# Launchpad_Board.net
KiCad netlist of a schematic drawn in EAGLE
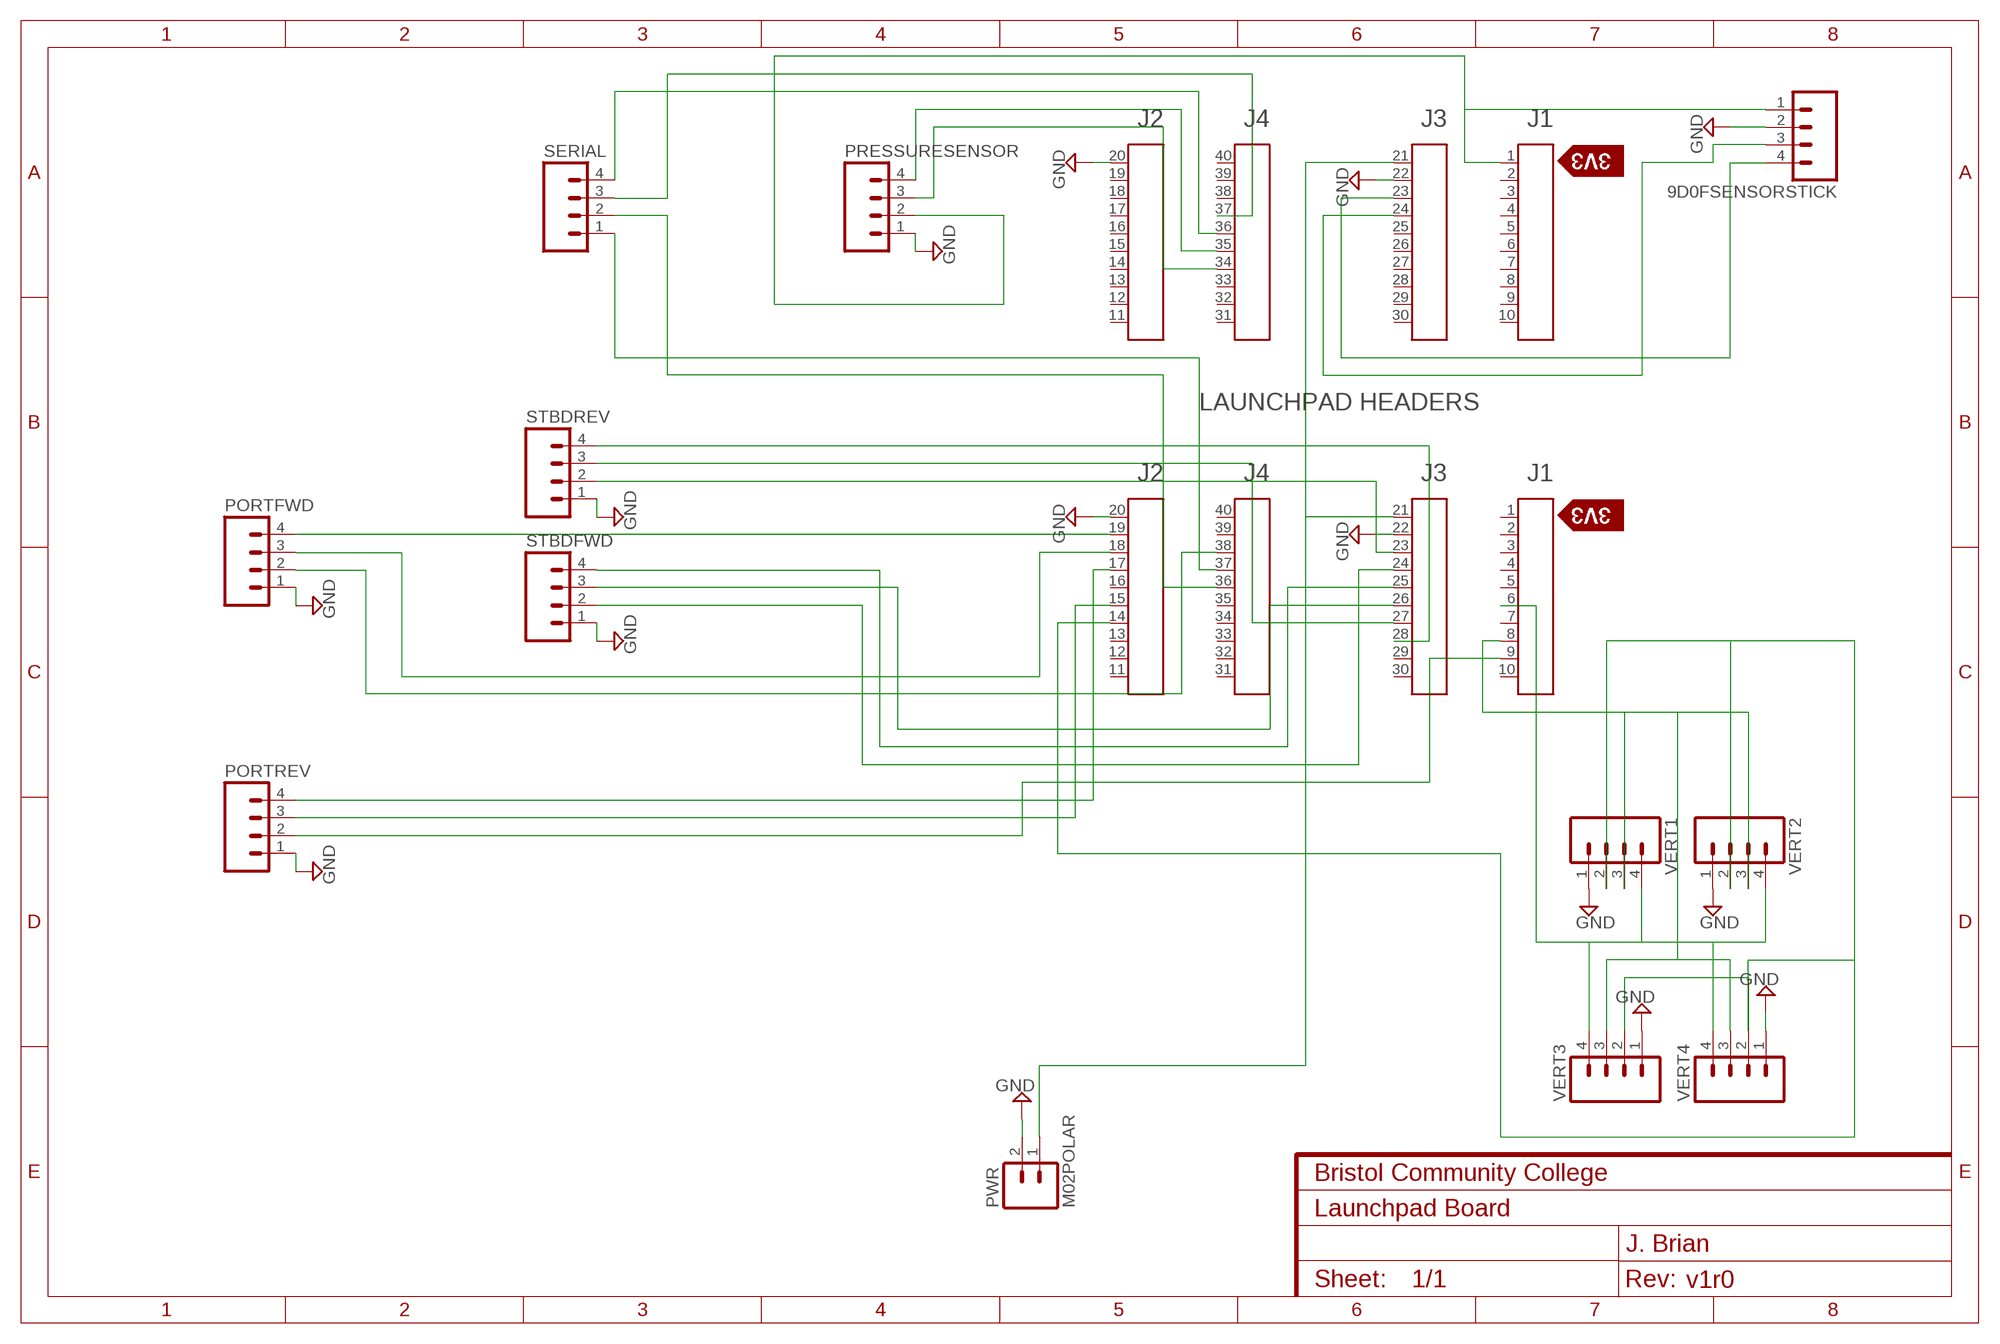
[diagram p0: schematic, sheet 1]

(export (version "E")
  (design (tool "Eeschema 10.0.6"))
  (components
    (comp (ref "9D0FSENSORSTICK")
      (value "M04PTH")
      (footprint "eagle-import:1X04")
      (libsource (lib "eagle-import") (part "M04PTH"))
    )
    (comp (ref "A1")
      (value "HEADER4X10-BOOSTERPACK")
      (footprint "eagle-import:4X10-BOOSTERPACK")
      (libsource (lib "eagle-import") (part "HEADER4X10-BOOSTERPACK"))
    )
    (comp (ref "A2")
      (value "HEADER4X10-BOOSTERPACK")
      (footprint "eagle-import:4X10-BOOSTERPACK")
      (libsource (lib "eagle-import") (part "HEADER4X10-BOOSTERPACK"))
    )
    (comp (ref "PORTFWD")
      (value "M04POLAR_LOCK")
      (footprint "eagle-import:MOLEX-1X4_LOCK")
      (libsource (lib "eagle-import") (part "M04POLAR_LOCK"))
    )
    (comp (ref "PORTREV")
      (value "M04POLAR_LOCK")
      (footprint "eagle-import:MOLEX-1X4_LOCK")
      (libsource (lib "eagle-import") (part "M04POLAR_LOCK"))
    )
    (comp (ref "PRESSURESENSOR")
      (value "M04POLAR")
      (footprint "eagle-import:MOLEX-1X4")
      (libsource (lib "eagle-import") (part "M04POLAR"))
    )
    (comp (ref "PWR")
      (value "M02POLAR")
      (footprint "eagle-import:MOLEX-1X2")
      (libsource (lib "eagle-import") (part "M02POLAR"))
    )
    (comp (ref "SERIAL")
      (value "M04POLAR_LOCK")
      (footprint "eagle-import:MOLEX-1X4_LOCK")
      (libsource (lib "eagle-import") (part "M04POLAR_LOCK"))
    )
    (comp (ref "STBDFWD")
      (value "M04POLAR_LOCK")
      (footprint "eagle-import:MOLEX-1X4_LOCK")
      (libsource (lib "eagle-import") (part "M04POLAR_LOCK"))
    )
    (comp (ref "STBDREV")
      (value "M04POLAR_LOCK")
      (footprint "eagle-import:MOLEX-1X4_LOCK")
      (libsource (lib "eagle-import") (part "M04POLAR_LOCK"))
    )
    (comp (ref "U$3")
      (value "SILK_3V3_TAG")
      (footprint "eagle-import:SILK_3V3_TAG")
      (libsource (lib "eagle-import") (part "SILK_3V3_TAG"))
    )
    (comp (ref "U$4")
      (value "SILK_3V3_TAG")
      (footprint "eagle-import:SILK_3V3_TAG")
      (libsource (lib "eagle-import") (part "SILK_3V3_TAG"))
    )
    (comp (ref "VERT1")
      (value "M04POLAR_LOCK")
      (footprint "eagle-import:MOLEX-1X4_LOCK")
      (libsource (lib "eagle-import") (part "M04POLAR_LOCK"))
    )
    (comp (ref "VERT2")
      (value "M04POLAR_LOCK")
      (footprint "eagle-import:MOLEX-1X4_LOCK")
      (libsource (lib "eagle-import") (part "M04POLAR_LOCK"))
    )
    (comp (ref "VERT3")
      (value "M04POLAR_LOCK")
      (footprint "eagle-import:MOLEX-1X4_LOCK")
      (libsource (lib "eagle-import") (part "M04POLAR_LOCK"))
    )
    (comp (ref "VERT4")
      (value "M04POLAR_LOCK")
      (footprint "eagle-import:MOLEX-1X4_LOCK")
      (libsource (lib "eagle-import") (part "M04POLAR_LOCK"))
    )
  )
  (nets
    (net (code "1") (name "/N$9") (class "Default")
      (node (ref "A2") (pin "8") (pinfunction "P$8_8") (pintype "bidirectional"))
      (node (ref "VERT1") (pin "3") (pinfunction "3_3") (pintype "passive"))
      (node (ref "VERT2") (pin "3") (pinfunction "3_3") (pintype "passive"))
      (node (ref "VERT3") (pin "3") (pinfunction "3_3") (pintype "passive"))
      (node (ref "VERT4") (pin "3") (pinfunction "3_3") (pintype "passive"))
    )
    (net (code "2") (name "GND") (class "Default")
      (node (ref "9D0FSENSORSTICK") (pin "2") (pinfunction "2_2") (pintype "passive"))
      (node (ref "A1") (pin "20") (pinfunction "P$20_20") (pintype "bidirectional"))
      (node (ref "A1") (pin "22") (pinfunction "P$22_22") (pintype "bidirectional"))
      (node (ref "A2") (pin "20") (pinfunction "P$20_20") (pintype "bidirectional"))
      (node (ref "A2") (pin "22") (pinfunction "P$22_22") (pintype "bidirectional"))
      (node (ref "PORTFWD") (pin "1") (pinfunction "1_1") (pintype "passive"))
      (node (ref "PORTREV") (pin "1") (pinfunction "1_1") (pintype "passive"))
      (node (ref "PRESSURESENSOR") (pin "1") (pinfunction "1_1") (pintype "passive"))
      (node (ref "PWR") (pin "2") (pinfunction "2_2") (pintype "passive"))
      (node (ref "STBDFWD") (pin "1") (pinfunction "1_1") (pintype "passive"))
      (node (ref "STBDREV") (pin "1") (pinfunction "1_1") (pintype "passive"))
      (node (ref "VERT1") (pin "1") (pinfunction "1_1") (pintype "passive"))
      (node (ref "VERT2") (pin "1") (pinfunction "1_1") (pintype "passive"))
      (node (ref "VERT3") (pin "1") (pinfunction "1_1") (pintype "passive"))
      (node (ref "VERT4") (pin "1") (pinfunction "1_1") (pintype "passive"))
    )
    (net (code "3") (name "Net-(A1-P$1)") (class "Default")
      (node (ref "9D0FSENSORSTICK") (pin "1") (pinfunction "1_1") (pintype "passive"))
      (node (ref "A1") (pin "1") (pinfunction "P$1_1") (pintype "bidirectional"))
      (node (ref "PRESSURESENSOR") (pin "2") (pinfunction "2_2") (pintype "passive"))
    )
    (net (code "4") (name "Net-(A1-P$21)") (class "Default")
      (node (ref "A1") (pin "21") (pinfunction "P$21_21") (pintype "bidirectional"))
      (node (ref "A2") (pin "21") (pinfunction "P$21_21") (pintype "bidirectional"))
      (node (ref "PWR") (pin "1") (pinfunction "1_1") (pintype "passive"))
    )
    (net (code "5") (name "Net-(A1-P$23)") (class "Default")
      (node (ref "9D0FSENSORSTICK") (pin "4") (pinfunction "4_4") (pintype "passive"))
      (node (ref "A1") (pin "23") (pinfunction "P$23_23") (pintype "bidirectional"))
    )
    (net (code "6") (name "Net-(A1-P$24)") (class "Default")
      (node (ref "9D0FSENSORSTICK") (pin "3") (pinfunction "3_3") (pintype "passive"))
      (node (ref "A1") (pin "24") (pinfunction "P$24_24") (pintype "bidirectional"))
    )
    (net (code "7") (name "Net-(A1-P$34)") (class "Default")
      (node (ref "A1") (pin "34") (pinfunction "P$34_34") (pintype "bidirectional"))
      (node (ref "PRESSURESENSOR") (pin "3") (pinfunction "3_3") (pintype "passive"))
    )
    (net (code "8") (name "Net-(A1-P$35)") (class "Default")
      (node (ref "A1") (pin "35") (pinfunction "P$35_35") (pintype "bidirectional"))
      (node (ref "PRESSURESENSOR") (pin "4") (pinfunction "4_4") (pintype "passive"))
    )
    (net (code "9") (name "Net-(A1-P$36)") (class "Default")
      (node (ref "A1") (pin "36") (pinfunction "P$36_36") (pintype "bidirectional"))
      (node (ref "SERIAL") (pin "4") (pinfunction "4_4") (pintype "passive"))
    )
    (net (code "10") (name "Net-(A1-P$37)") (class "Default")
      (node (ref "A1") (pin "37") (pinfunction "P$37_37") (pintype "bidirectional"))
      (node (ref "SERIAL") (pin "3") (pinfunction "3_3") (pintype "passive"))
    )
    (net (code "11") (name "Net-(A2-P$6)") (class "Default")
      (node (ref "A2") (pin "6") (pinfunction "P$6_6") (pintype "bidirectional"))
      (node (ref "VERT1") (pin "4") (pinfunction "4_4") (pintype "passive"))
      (node (ref "VERT2") (pin "4") (pinfunction "4_4") (pintype "passive"))
      (node (ref "VERT3") (pin "4") (pinfunction "4_4") (pintype "passive"))
      (node (ref "VERT4") (pin "4") (pinfunction "4_4") (pintype "passive"))
    )
    (net (code "12") (name "Net-(A2-P$9)") (class "Default")
      (node (ref "A2") (pin "9") (pinfunction "P$9_9") (pintype "bidirectional"))
      (node (ref "PORTREV") (pin "2") (pinfunction "2_2") (pintype "passive"))
    )
    (net (code "13") (name "Net-(A2-P$14)") (class "Default")
      (node (ref "A2") (pin "14") (pinfunction "P$14_14") (pintype "bidirectional"))
      (node (ref "VERT1") (pin "2") (pinfunction "2_2") (pintype "passive"))
      (node (ref "VERT2") (pin "2") (pinfunction "2_2") (pintype "passive"))
      (node (ref "VERT3") (pin "2") (pinfunction "2_2") (pintype "passive"))
      (node (ref "VERT4") (pin "2") (pinfunction "2_2") (pintype "passive"))
    )
    (net (code "14") (name "Net-(A2-P$15)") (class "Default")
      (node (ref "A2") (pin "15") (pinfunction "P$15_15") (pintype "bidirectional"))
      (node (ref "PORTREV") (pin "3") (pinfunction "3_3") (pintype "passive"))
    )
    (net (code "15") (name "Net-(A2-P$17)") (class "Default")
      (node (ref "A2") (pin "17") (pinfunction "P$17_17") (pintype "bidirectional"))
      (node (ref "PORTREV") (pin "4") (pinfunction "4_4") (pintype "passive"))
    )
    (net (code "16") (name "Net-(A2-P$18)") (class "Default")
      (node (ref "A2") (pin "18") (pinfunction "P$18_18") (pintype "bidirectional"))
      (node (ref "PORTFWD") (pin "3") (pinfunction "3_3") (pintype "passive"))
    )
    (net (code "17") (name "Net-(A2-P$19)") (class "Default")
      (node (ref "A2") (pin "19") (pinfunction "P$19_19") (pintype "bidirectional"))
      (node (ref "PORTFWD") (pin "4") (pinfunction "4_4") (pintype "passive"))
    )
    (net (code "18") (name "Net-(A2-P$23)") (class "Default")
      (node (ref "A2") (pin "23") (pinfunction "P$23_23") (pintype "bidirectional"))
      (node (ref "STBDREV") (pin "2") (pinfunction "2_2") (pintype "passive"))
    )
    (net (code "19") (name "Net-(A2-P$24)") (class "Default")
      (node (ref "A2") (pin "24") (pinfunction "P$24_24") (pintype "bidirectional"))
      (node (ref "STBDFWD") (pin "2") (pinfunction "2_2") (pintype "passive"))
    )
    (net (code "20") (name "Net-(A2-P$25)") (class "Default")
      (node (ref "A2") (pin "25") (pinfunction "P$25_25") (pintype "bidirectional"))
      (node (ref "STBDFWD") (pin "4") (pinfunction "4_4") (pintype "passive"))
    )
    (net (code "21") (name "Net-(A2-P$26)") (class "Default")
      (node (ref "A2") (pin "26") (pinfunction "P$26_26") (pintype "bidirectional"))
      (node (ref "STBDFWD") (pin "3") (pinfunction "3_3") (pintype "passive"))
    )
    (net (code "22") (name "Net-(A2-P$27)") (class "Default")
      (node (ref "A2") (pin "27") (pinfunction "P$27_27") (pintype "bidirectional"))
      (node (ref "STBDREV") (pin "3") (pinfunction "3_3") (pintype "passive"))
    )
    (net (code "23") (name "Net-(A2-P$28)") (class "Default")
      (node (ref "A2") (pin "28") (pinfunction "P$28_28") (pintype "bidirectional"))
      (node (ref "STBDREV") (pin "4") (pinfunction "4_4") (pintype "passive"))
    )
    (net (code "24") (name "Net-(A2-P$36)") (class "Default")
      (node (ref "A2") (pin "36") (pinfunction "P$36_36") (pintype "bidirectional"))
      (node (ref "SERIAL") (pin "2") (pinfunction "2_2") (pintype "passive"))
    )
    (net (code "25") (name "Net-(A2-P$37)") (class "Default")
      (node (ref "A2") (pin "37") (pinfunction "P$37_37") (pintype "bidirectional"))
      (node (ref "SERIAL") (pin "1") (pinfunction "1_1") (pintype "passive"))
    )
    (net (code "26") (name "Net-(A2-P$38)") (class "Default")
      (node (ref "A2") (pin "38") (pinfunction "P$38_38") (pintype "bidirectional"))
      (node (ref "PORTFWD") (pin "2") (pinfunction "2_2") (pintype "passive"))
    )
    (net (code "27") (name "unconnected-(A1-P$2-Pad2)") (class "Default")
      (node (ref "A1") (pin "2") (pinfunction "P$2_2") (pintype "bidirectional"))
    )
    (net (code "28") (name "unconnected-(A1-P$3-Pad3)") (class "Default")
      (node (ref "A1") (pin "3") (pinfunction "P$3_3") (pintype "bidirectional"))
    )
    (net (code "29") (name "unconnected-(A1-P$4-Pad4)") (class "Default")
      (node (ref "A1") (pin "4") (pinfunction "P$4_4") (pintype "bidirectional"))
    )
    (net (code "30") (name "unconnected-(A1-P$5-Pad5)") (class "Default")
      (node (ref "A1") (pin "5") (pinfunction "P$5_5") (pintype "bidirectional"))
    )
    (net (code "31") (name "unconnected-(A1-P$6-Pad6)") (class "Default")
      (node (ref "A1") (pin "6") (pinfunction "P$6_6") (pintype "bidirectional"))
    )
    (net (code "32") (name "unconnected-(A1-P$7-Pad7)") (class "Default")
      (node (ref "A1") (pin "7") (pinfunction "P$7_7") (pintype "bidirectional"))
    )
    (net (code "33") (name "unconnected-(A1-P$8-Pad8)") (class "Default")
      (node (ref "A1") (pin "8") (pinfunction "P$8_8") (pintype "bidirectional"))
    )
    (net (code "34") (name "unconnected-(A1-P$9-Pad9)") (class "Default")
      (node (ref "A1") (pin "9") (pinfunction "P$9_9") (pintype "bidirectional"))
    )
    (net (code "35") (name "unconnected-(A1-P$10-Pad10)") (class "Default")
      (node (ref "A1") (pin "10") (pinfunction "P$10_10") (pintype "bidirectional"))
    )
    (net (code "36") (name "unconnected-(A1-P$11-Pad11)") (class "Default")
      (node (ref "A1") (pin "11") (pinfunction "P$11_11") (pintype "bidirectional"))
    )
    (net (code "37") (name "unconnected-(A1-P$12-Pad12)") (class "Default")
      (node (ref "A1") (pin "12") (pinfunction "P$12_12") (pintype "bidirectional"))
    )
    (net (code "38") (name "unconnected-(A1-P$13-Pad13)") (class "Default")
      (node (ref "A1") (pin "13") (pinfunction "P$13_13") (pintype "bidirectional"))
    )
    (net (code "39") (name "unconnected-(A1-P$14-Pad14)") (class "Default")
      (node (ref "A1") (pin "14") (pinfunction "P$14_14") (pintype "bidirectional"))
    )
    (net (code "40") (name "unconnected-(A1-P$15-Pad15)") (class "Default")
      (node (ref "A1") (pin "15") (pinfunction "P$15_15") (pintype "bidirectional"))
    )
    (net (code "41") (name "unconnected-(A1-P$16-Pad16)") (class "Default")
      (node (ref "A1") (pin "16") (pinfunction "P$16_16") (pintype "bidirectional"))
    )
    (net (code "42") (name "unconnected-(A1-P$17-Pad17)") (class "Default")
      (node (ref "A1") (pin "17") (pinfunction "P$17_17") (pintype "bidirectional"))
    )
    (net (code "43") (name "unconnected-(A1-P$18-Pad18)") (class "Default")
      (node (ref "A1") (pin "18") (pinfunction "P$18_18") (pintype "bidirectional"))
    )
    (net (code "44") (name "unconnected-(A1-P$19-Pad19)") (class "Default")
      (node (ref "A1") (pin "19") (pinfunction "P$19_19") (pintype "bidirectional"))
    )
    (net (code "45") (name "unconnected-(A1-P$25-Pad25)") (class "Default")
      (node (ref "A1") (pin "25") (pinfunction "P$25_25") (pintype "bidirectional"))
    )
    (net (code "46") (name "unconnected-(A1-P$26-Pad26)") (class "Default")
      (node (ref "A1") (pin "26") (pinfunction "P$26_26") (pintype "bidirectional"))
    )
    (net (code "47") (name "unconnected-(A1-P$27-Pad27)") (class "Default")
      (node (ref "A1") (pin "27") (pinfunction "P$27_27") (pintype "bidirectional"))
    )
    (net (code "48") (name "unconnected-(A1-P$28-Pad28)") (class "Default")
      (node (ref "A1") (pin "28") (pinfunction "P$28_28") (pintype "bidirectional"))
    )
    (net (code "49") (name "unconnected-(A1-P$29-Pad29)") (class "Default")
      (node (ref "A1") (pin "29") (pinfunction "P$29_29") (pintype "bidirectional"))
    )
    (net (code "50") (name "unconnected-(A1-P$30-Pad30)") (class "Default")
      (node (ref "A1") (pin "30") (pinfunction "P$30_30") (pintype "bidirectional"))
    )
    (net (code "51") (name "unconnected-(A1-P$31-Pad31)") (class "Default")
      (node (ref "A1") (pin "31") (pinfunction "P$31_31") (pintype "bidirectional"))
    )
    (net (code "52") (name "unconnected-(A1-P$32-Pad32)") (class "Default")
      (node (ref "A1") (pin "32") (pinfunction "P$32_32") (pintype "bidirectional"))
    )
    (net (code "53") (name "unconnected-(A1-P$33-Pad33)") (class "Default")
      (node (ref "A1") (pin "33") (pinfunction "P$33_33") (pintype "bidirectional"))
    )
    (net (code "54") (name "unconnected-(A1-P$38-Pad38)") (class "Default")
      (node (ref "A1") (pin "38") (pinfunction "P$38_38") (pintype "bidirectional"))
    )
    (net (code "55") (name "unconnected-(A1-P$39-Pad39)") (class "Default")
      (node (ref "A1") (pin "39") (pinfunction "P$39_39") (pintype "bidirectional"))
    )
    (net (code "56") (name "unconnected-(A1-P$40-Pad40)") (class "Default")
      (node (ref "A1") (pin "40") (pinfunction "P$40_40") (pintype "bidirectional"))
    )
    (net (code "57") (name "unconnected-(A2-P$1-Pad1)") (class "Default")
      (node (ref "A2") (pin "1") (pinfunction "P$1_1") (pintype "bidirectional"))
    )
    (net (code "58") (name "unconnected-(A2-P$2-Pad2)") (class "Default")
      (node (ref "A2") (pin "2") (pinfunction "P$2_2") (pintype "bidirectional"))
    )
    (net (code "59") (name "unconnected-(A2-P$3-Pad3)") (class "Default")
      (node (ref "A2") (pin "3") (pinfunction "P$3_3") (pintype "bidirectional"))
    )
    (net (code "60") (name "unconnected-(A2-P$4-Pad4)") (class "Default")
      (node (ref "A2") (pin "4") (pinfunction "P$4_4") (pintype "bidirectional"))
    )
    (net (code "61") (name "unconnected-(A2-P$5-Pad5)") (class "Default")
      (node (ref "A2") (pin "5") (pinfunction "P$5_5") (pintype "bidirectional"))
    )
    (net (code "62") (name "unconnected-(A2-P$7-Pad7)") (class "Default")
      (node (ref "A2") (pin "7") (pinfunction "P$7_7") (pintype "bidirectional"))
    )
    (net (code "63") (name "unconnected-(A2-P$10-Pad10)") (class "Default")
      (node (ref "A2") (pin "10") (pinfunction "P$10_10") (pintype "bidirectional"))
    )
    (net (code "64") (name "unconnected-(A2-P$11-Pad11)") (class "Default")
      (node (ref "A2") (pin "11") (pinfunction "P$11_11") (pintype "bidirectional"))
    )
    (net (code "65") (name "unconnected-(A2-P$12-Pad12)") (class "Default")
      (node (ref "A2") (pin "12") (pinfunction "P$12_12") (pintype "bidirectional"))
    )
    (net (code "66") (name "unconnected-(A2-P$13-Pad13)") (class "Default")
      (node (ref "A2") (pin "13") (pinfunction "P$13_13") (pintype "bidirectional"))
    )
    (net (code "67") (name "unconnected-(A2-P$16-Pad16)") (class "Default")
      (node (ref "A2") (pin "16") (pinfunction "P$16_16") (pintype "bidirectional"))
    )
    (net (code "68") (name "unconnected-(A2-P$29-Pad29)") (class "Default")
      (node (ref "A2") (pin "29") (pinfunction "P$29_29") (pintype "bidirectional"))
    )
    (net (code "69") (name "unconnected-(A2-P$30-Pad30)") (class "Default")
      (node (ref "A2") (pin "30") (pinfunction "P$30_30") (pintype "bidirectional"))
    )
    (net (code "70") (name "unconnected-(A2-P$31-Pad31)") (class "Default")
      (node (ref "A2") (pin "31") (pinfunction "P$31_31") (pintype "bidirectional"))
    )
    (net (code "71") (name "unconnected-(A2-P$32-Pad32)") (class "Default")
      (node (ref "A2") (pin "32") (pinfunction "P$32_32") (pintype "bidirectional"))
    )
    (net (code "72") (name "unconnected-(A2-P$33-Pad33)") (class "Default")
      (node (ref "A2") (pin "33") (pinfunction "P$33_33") (pintype "bidirectional"))
    )
    (net (code "73") (name "unconnected-(A2-P$34-Pad34)") (class "Default")
      (node (ref "A2") (pin "34") (pinfunction "P$34_34") (pintype "bidirectional"))
    )
    (net (code "74") (name "unconnected-(A2-P$35-Pad35)") (class "Default")
      (node (ref "A2") (pin "35") (pinfunction "P$35_35") (pintype "bidirectional"))
    )
    (net (code "75") (name "unconnected-(A2-P$39-Pad39)") (class "Default")
      (node (ref "A2") (pin "39") (pinfunction "P$39_39") (pintype "bidirectional"))
    )
    (net (code "76") (name "unconnected-(A2-P$40-Pad40)") (class "Default")
      (node (ref "A2") (pin "40") (pinfunction "P$40_40") (pintype "bidirectional"))
    )
  )
)
